# esp-temperature.net
KiCad netlist of a schematic drawn in EAGLE
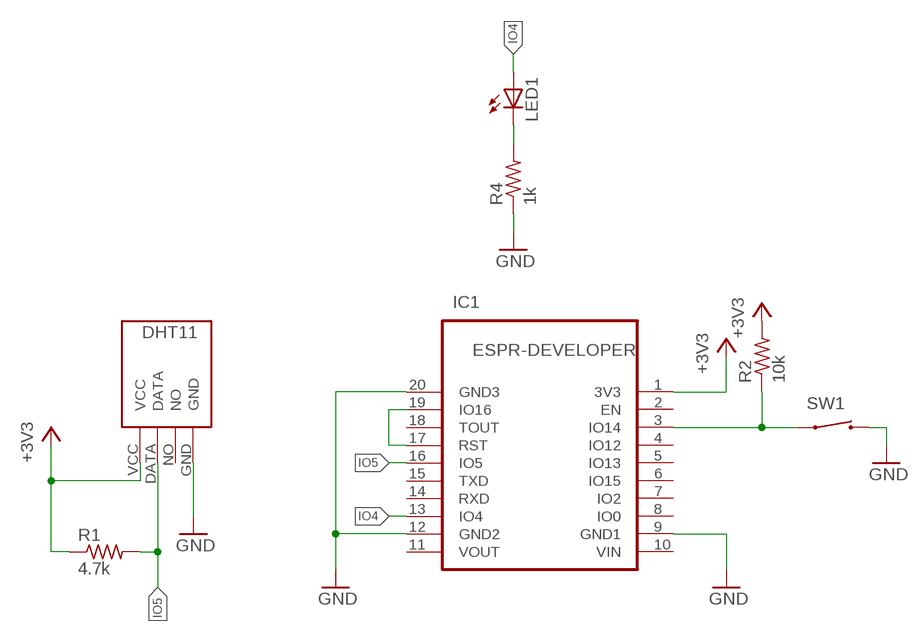
[diagram p0: schematic, sheet 1]

(export (version "E")
  (design (tool "Eeschema 10.0.6"))
  (components
    (comp (ref "IC1")
      (value "ESPR-DEVELOPER")
      (footprint "eagle-import:ESPR-DEVELOPER")
      (libsource (lib "eagle-import") (part "ESPR-DEVELOPER"))
    )
    (comp (ref "LED1")
      (value "LED-SIDEUP2")
      (footprint "eagle-import:LED5MM-SIDE-UP2")
      (libsource (lib "eagle-import") (part "LED-SIDEUP2"))
    )
    (comp (ref "R1")
      (value "4.7k")
      (footprint "eagle-import:R0805")
      (libsource (lib "eagle-import") (part "R-US_R0805"))
    )
    (comp (ref "R2")
      (value "10k")
      (footprint "eagle-import:R0805")
      (libsource (lib "eagle-import") (part "R-US_R0805"))
    )
    (comp (ref "R4")
      (value "1k")
      (footprint "eagle-import:R0805")
      (libsource (lib "eagle-import") (part "R-US_R0805"))
    )
    (comp (ref "SW1")
      (value "TVBP06")
      (footprint "eagle-import:TVBP06")
      (libsource (lib "eagle-import") (part "TVBP06"))
    )
    (comp (ref "U$1")
      (value "DHT11")
      (footprint "eagle-import:DHT11")
      (libsource (lib "eagle-import") (part "DHT11"))
    )
  )
  (nets
    (net (code "1") (name "+3V3") (class "Default")
      (node (ref "IC1") (pin "1") (pinfunction "3V3_1") (pintype "power_in"))
      (node (ref "R1") (pin "1") (pinfunction "1_1") (pintype "passive"))
      (node (ref "R2") (pin "2") (pinfunction "2_2") (pintype "passive"))
      (node (ref "U$1") (pin "VCC") (pinfunction "VCC_VCC") (pintype "bidirectional"))
    )
    (net (code "2") (name "/VIN") (class "Default")
      (node (ref "IC1") (pin "10") (pinfunction "VIN_10") (pintype "power_in"))
    )
    (net (code "3") (name "/VOUT") (class "Default")
      (node (ref "IC1") (pin "11") (pinfunction "VOUT_11") (pintype "power_in"))
    )
    (net (code "4") (name "GND") (class "Default")
      (node (ref "IC1") (pin "12") (pinfunction "GND2_12") (pintype "power_in"))
      (node (ref "IC1") (pin "20") (pinfunction "GND3_20") (pintype "power_in"))
      (node (ref "IC1") (pin "9") (pinfunction "GND1_9") (pintype "power_in"))
      (node (ref "R4") (pin "1") (pinfunction "1_1") (pintype "passive"))
      (node (ref "SW1") (pin "2") (pinfunction "2_2") (pintype "passive"))
      (node (ref "U$1") (pin "GND") (pinfunction "GND_GND") (pintype "bidirectional"))
    )
    (net (code "5") (name "IO4") (class "Default")
      (node (ref "IC1") (pin "13") (pinfunction "IO4_13") (pintype "bidirectional"))
      (node (ref "LED1") (pin "A") (pinfunction "A_A") (pintype "passive"))
    )
    (net (code "6") (name "IO5") (class "Default")
      (node (ref "IC1") (pin "16") (pinfunction "IO5_16") (pintype "open_collector"))
      (node (ref "R1") (pin "2") (pinfunction "2_2") (pintype "passive"))
      (node (ref "U$1") (pin "DATA") (pinfunction "DATA_DATA") (pintype "bidirectional"))
    )
    (net (code "7") (name "Net-(IC1-IO14)") (class "Default")
      (node (ref "IC1") (pin "3") (pinfunction "IO14_3") (pintype "bidirectional"))
      (node (ref "R2") (pin "1") (pinfunction "1_1") (pintype "passive"))
      (node (ref "SW1") (pin "1") (pinfunction "1_1") (pintype "passive"))
    )
    (net (code "8") (name "Net-(IC1-IO16)") (class "Default")
      (node (ref "IC1") (pin "17") (pinfunction "RST_17") (pintype "bidirectional"))
      (node (ref "IC1") (pin "19") (pinfunction "IO16_19") (pintype "bidirectional"))
    )
    (net (code "9") (name "Net-(LED1-C)") (class "Default")
      (node (ref "LED1") (pin "K") (pinfunction "C_K") (pintype "passive"))
      (node (ref "R4") (pin "2") (pinfunction "2_2") (pintype "passive"))
    )
    (net (code "10") (name "unconnected-(IC1-EN-Pad2)") (class "Default")
      (node (ref "IC1") (pin "2") (pinfunction "EN_2") (pintype "bidirectional"))
    )
    (net (code "11") (name "unconnected-(IC1-IO0-Pad8)") (class "Default")
      (node (ref "IC1") (pin "8") (pinfunction "IO0_8") (pintype "bidirectional"))
    )
    (net (code "12") (name "unconnected-(IC1-IO2-Pad7)") (class "Default")
      (node (ref "IC1") (pin "7") (pinfunction "IO2_7") (pintype "bidirectional"))
    )
    (net (code "13") (name "unconnected-(IC1-IO12-Pad4)") (class "Default")
      (node (ref "IC1") (pin "4") (pinfunction "IO12_4") (pintype "bidirectional"))
    )
    (net (code "14") (name "unconnected-(IC1-IO13-Pad5)") (class "Default")
      (node (ref "IC1") (pin "5") (pinfunction "IO13_5") (pintype "bidirectional"))
    )
    (net (code "15") (name "unconnected-(IC1-IO15-Pad6)") (class "Default")
      (node (ref "IC1") (pin "6") (pinfunction "IO15_6") (pintype "bidirectional"))
    )
    (net (code "16") (name "unconnected-(IC1-RXD-Pad14)") (class "Default")
      (node (ref "IC1") (pin "14") (pinfunction "RXD_14") (pintype "bidirectional"))
    )
    (net (code "17") (name "unconnected-(IC1-TOUT-Pad18)") (class "Default")
      (node (ref "IC1") (pin "18") (pinfunction "TOUT_18") (pintype "bidirectional"))
    )
    (net (code "18") (name "unconnected-(IC1-TXD-Pad15)") (class "Default")
      (node (ref "IC1") (pin "15") (pinfunction "TXD_15") (pintype "bidirectional"))
    )
    (net (code "19") (name "unconnected-(U$1-PadNO)") (class "Default")
      (node (ref "U$1") (pin "NO") (pinfunction "NO_NO") (pintype "bidirectional"))
    )
  )
)
